# PID.net
KiCad netlist of a schematic drawn in EasyEDA Pro
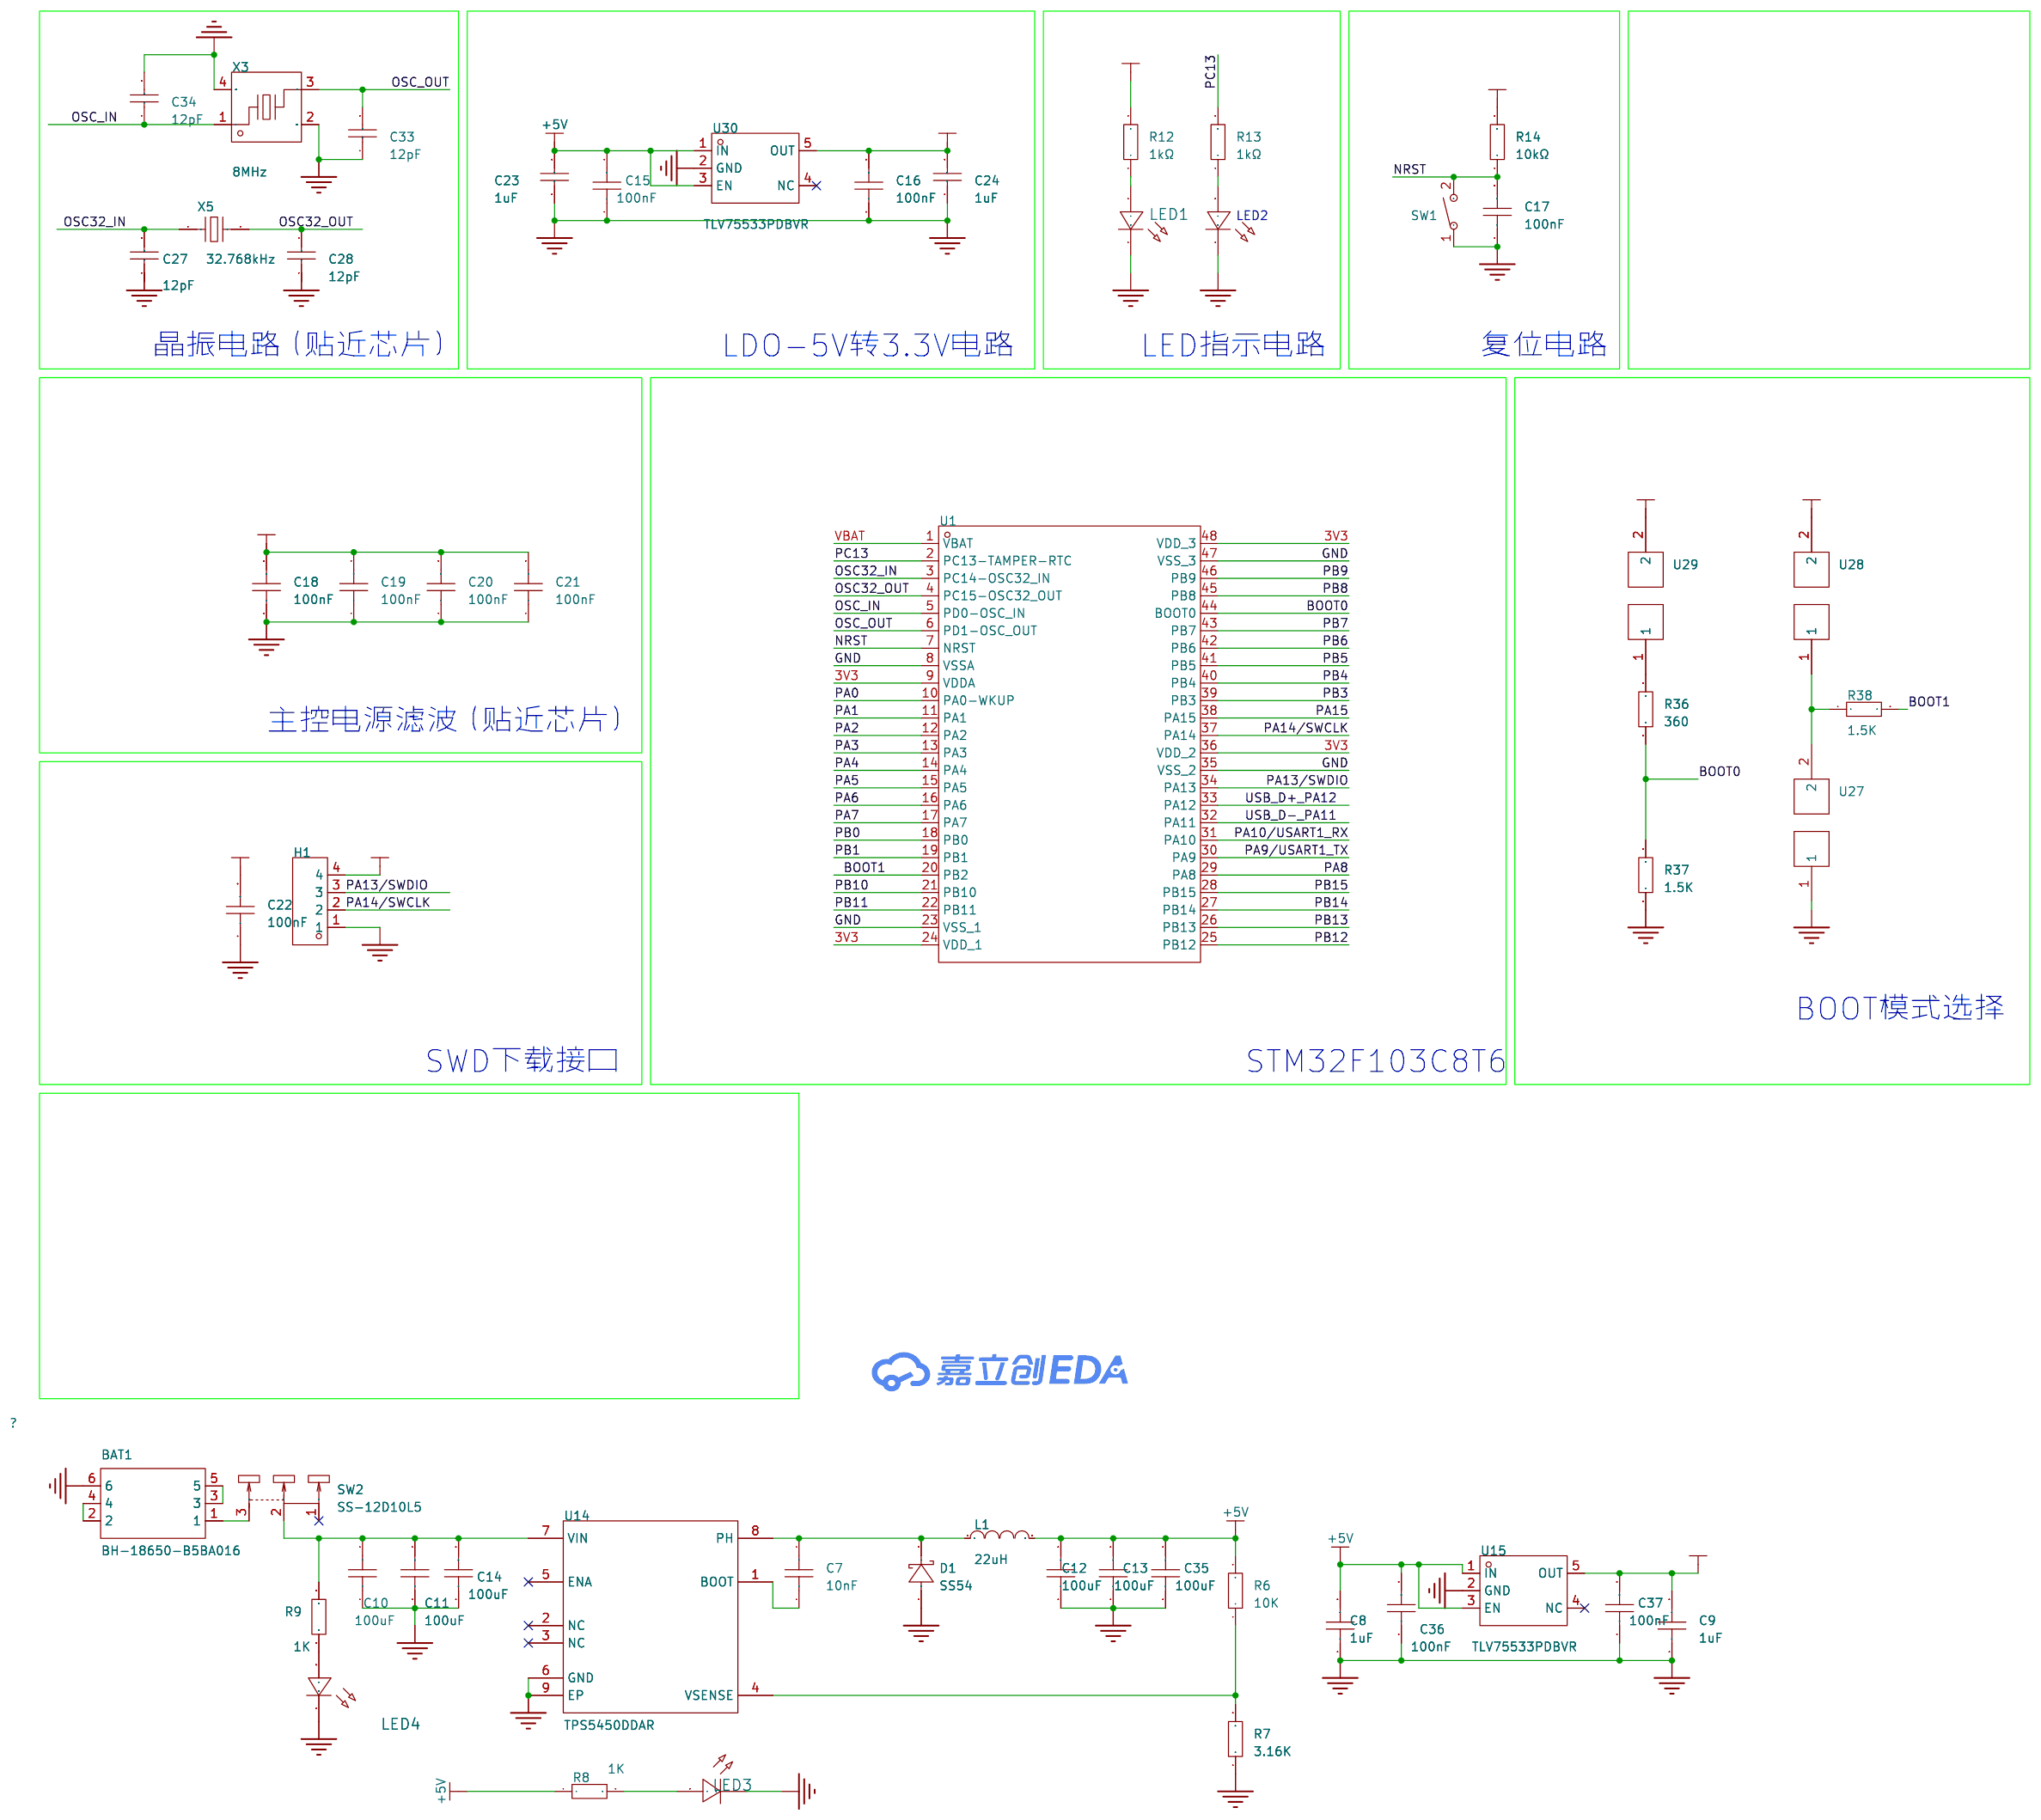
[diagram p0: schematic sheet]

(export (version "E")
  (design (tool "Eeschema 10.0.6"))
  (components
    (comp (ref "BAT1")
      (value "BH-18650-B5BA016")
      (footprint "easyedapro:BAT-SMD_BH-18650-B5BA016")
      (description "连接器类型:电池盒;适用电池规格:-;触点电镀:金;工作温度范围:-25°C~+85°C;")
      (fields (field (name "Manufacturer") "MYOUNG(美阳)"))
      (libsource (lib "easyedapro") (part "BH-18650-B5BA016"))
    )
    (comp (ref "C7")
      (value "100nF")
      (footprint "easyedapro:C0603")
      (libsource (lib "easyedapro") (part "CapAcitance"))
    )
    (comp (ref "C8")
      (value "100nF")
      (footprint "easyedapro:C0603")
      (libsource (lib "easyedapro") (part "CapAcitance"))
    )
    (comp (ref "C9")
      (value "100nF")
      (footprint "easyedapro:C0603")
      (libsource (lib "easyedapro") (part "CapAcitance"))
    )
    (comp (ref "C10")
      (value "100uF")
      (footprint "easyedapro:C1206")
      (description "容值:100uF;精度:±20%;额定电压:10V;材质(温度系数):X5R;")
      (fields
        (field (name "Manufacturer Part") "HGC1206R5107M100NSPJ")
        (field (name "Manufacturer") "Chinocera(华瓷)")
      )
      (libsource (lib "easyedapro") (part "HGC1206R5107M100NSPJ"))
    )
    (comp (ref "C11")
      (value "100uF")
      (footprint "easyedapro:C1206")
      (description "容值:100uF;精度:±20%;额定电压:10V;材质(温度系数):X5R;")
      (fields
        (field (name "Manufacturer Part") "HGC1206R5107M100NSPJ")
        (field (name "Manufacturer") "Chinocera(华瓷)")
      )
      (libsource (lib "easyedapro") (part "HGC1206R5107M100NSPJ"))
    )
    (comp (ref "C12")
      (value "100uF")
      (footprint "easyedapro:C1206")
      (description "容值:100uF;精度:±20%;额定电压:10V;材质(温度系数):X5R;")
      (fields
        (field (name "Manufacturer Part") "HGC1206R5107M100NSPJ")
        (field (name "Manufacturer") "Chinocera(华瓷)")
      )
      (libsource (lib "easyedapro") (part "HGC1206R5107M100NSPJ"))
    )
    (comp (ref "C13")
      (value "100uF")
      (footprint "easyedapro:C1206")
      (description "容值:100uF;精度:±20%;额定电压:10V;材质(温度系数):X5R;")
      (fields
        (field (name "Manufacturer Part") "HGC1206R5107M100NSPJ")
        (field (name "Manufacturer") "Chinocera(华瓷)")
      )
      (libsource (lib "easyedapro") (part "HGC1206R5107M100NSPJ"))
    )
    (comp (ref "C14")
      (value "100uF")
      (footprint "easyedapro:C1206")
      (description "容值:100uF;精度:±20%;额定电压:10V;材质(温度系数):X5R;")
      (fields
        (field (name "Manufacturer Part") "HGC1206R5107M100NSPJ")
        (field (name "Manufacturer") "Chinocera(华瓷)")
      )
      (libsource (lib "easyedapro") (part "HGC1206R5107M100NSPJ"))
    )
    (comp (ref "C15")
      (value "100nF")
      (footprint "easyedapro:C0402")
      (description "容值:100nF;精度:±10%;额定电压:50V;材质(温度系数):X7R;")
      (fields
        (field (name "Manufacturer Part") "GRM155R71H104KE14D")
        (field (name "Manufacturer") "muRata(村田)")
      )
      (libsource (lib "easyedapro") (part "GRM155R71H104KE14D"))
    )
    (comp (ref "C16")
      (value "100nF")
      (footprint "easyedapro:C0402")
      (description "容值:100nF;精度:±10%;额定电压:50V;材质(温度系数):X7R;")
      (fields
        (field (name "Manufacturer Part") "GRM155R71H104KE14D")
        (field (name "Manufacturer") "muRata(村田)")
      )
      (libsource (lib "easyedapro") (part "GRM155R71H104KE14D"))
    )
    (comp (ref "C17")
      (value "100nF")
      (footprint "easyedapro:C0402")
      (description "容值:100nF;精度:±10%;额定电压:50V;材质(温度系数):X7R;")
      (fields
        (field (name "Manufacturer Part") "GRM155R71H104KE14D")
        (field (name "Manufacturer") "muRata(村田)")
      )
      (libsource (lib "easyedapro") (part "GRM155R71H104KE14D"))
    )
    (comp (ref "C18")
      (value "100nF")
      (footprint "easyedapro:C0402")
      (description "容值:100nF;精度:±10%;额定电压:50V;材质(温度系数):X7R;")
      (fields
        (field (name "Manufacturer Part") "GRM155R71H104KE14D")
        (field (name "Manufacturer") "muRata(村田)")
      )
      (libsource (lib "easyedapro") (part "GRM155R71H104KE14D"))
    )
    (comp (ref "C19")
      (value "100nF")
      (footprint "easyedapro:C0402")
      (description "容值:100nF;精度:±10%;额定电压:50V;材质(温度系数):X7R;")
      (fields
        (field (name "Manufacturer Part") "GRM155R71H104KE14D")
        (field (name "Manufacturer") "muRata(村田)")
      )
      (libsource (lib "easyedapro") (part "GRM155R71H104KE14D"))
    )
    (comp (ref "C20")
      (value "100nF")
      (footprint "easyedapro:C0402")
      (description "容值:100nF;精度:±10%;额定电压:50V;材质(温度系数):X7R;")
      (fields
        (field (name "Manufacturer Part") "GRM155R71H104KE14D")
        (field (name "Manufacturer") "muRata(村田)")
      )
      (libsource (lib "easyedapro") (part "GRM155R71H104KE14D"))
    )
    (comp (ref "C21")
      (value "100nF")
      (footprint "easyedapro:C0402")
      (description "容值:100nF;精度:±10%;额定电压:50V;材质(温度系数):X7R;")
      (fields
        (field (name "Manufacturer Part") "GRM155R71H104KE14D")
        (field (name "Manufacturer") "muRata(村田)")
      )
      (libsource (lib "easyedapro") (part "GRM155R71H104KE14D"))
    )
    (comp (ref "C22")
      (value "100nF")
      (footprint "easyedapro:C0402")
      (description "容值:100nF;精度:±10%;额定电压:50V;材质(温度系数):X7R;")
      (fields
        (field (name "Manufacturer Part") "GRM155R71H104KE14D")
        (field (name "Manufacturer") "muRata(村田)")
      )
      (libsource (lib "easyedapro") (part "GRM155R71H104KE14D"))
    )
    (comp (ref "C23")
      (value "1uF")
      (footprint "easyedapro:C0402")
      (description "容值:1uF;精度:±10%;额定电压:10V;材质(温度系数):X5R;")
      (fields
        (field (name "Manufacturer Part") "CL05A105KP5NNNC")
        (field (name "Manufacturer") "SAMSUNG(三星)")
      )
      (libsource (lib "easyedapro") (part "CL05A105KP5NNNC"))
    )
    (comp (ref "C24")
      (value "1uF")
      (footprint "easyedapro:C0402")
      (description "容值:1uF;精度:±10%;额定电压:10V;材质(温度系数):X5R;")
      (fields
        (field (name "Manufacturer Part") "CL05A105KP5NNNC")
        (field (name "Manufacturer") "SAMSUNG(三星)")
      )
      (libsource (lib "easyedapro") (part "CL05A105KP5NNNC"))
    )
    (comp (ref "C27")
      (value "12pF")
      (footprint "easyedapro:C0402")
      (description "容值:12pF;精度:±5%;额定电压:50V;材质(温度系数):C0G;")
      (fields (field (name "Manufacturer Part") "0402CG120J500NT") (field (name "Manufacturer") "FH(风华)"))
      (libsource (lib "easyedapro") (part "0402CG120J500NT"))
    )
    (comp (ref "C28")
      (value "12pF")
      (footprint "easyedapro:C0402")
      (description "容值:12pF;精度:±5%;额定电压:50V;材质(温度系数):C0G;")
      (fields (field (name "Manufacturer Part") "0402CG120J500NT") (field (name "Manufacturer") "FH(风华)"))
      (libsource (lib "easyedapro") (part "0402CG120J500NT"))
    )
    (comp (ref "C33")
      (value "12pF")
      (footprint "easyedapro:C0402")
      (description "容值:12pF;精度:±5%;额定电压:50V;材质(温度系数):C0G;")
      (fields (field (name "Manufacturer Part") "0402CG120J500NT") (field (name "Manufacturer") "FH(风华)"))
      (libsource (lib "easyedapro") (part "0402CG120J500NT"))
    )
    (comp (ref "C34")
      (value "12pF")
      (footprint "easyedapro:C0402")
      (description "容值:12pF;精度:±5%;额定电压:50V;材质(温度系数):C0G;")
      (fields (field (name "Manufacturer Part") "0402CG120J500NT") (field (name "Manufacturer") "FH(风华)"))
      (libsource (lib "easyedapro") (part "0402CG120J500NT"))
    )
    (comp (ref "C35")
      (value "100uF")
      (footprint "easyedapro:C1206")
      (description "容值:100uF;精度:±20%;额定电压:10V;材质(温度系数):X5R;")
      (fields
        (field (name "Manufacturer Part") "HGC1206R5107M100NSPJ")
        (field (name "Manufacturer") "Chinocera(华瓷)")
      )
      (libsource (lib "easyedapro") (part "HGC1206R5107M100NSPJ"))
    )
    (comp (ref "C36")
      (value "100nF")
      (footprint "easyedapro:C0402")
      (description "容值:100nF;精度:±10%;额定电压:50V;材质(温度系数):X7R;")
      (fields
        (field (name "Manufacturer Part") "GRM155R71H104KE14D")
        (field (name "Manufacturer") "muRata(村田)")
      )
      (libsource (lib "easyedapro") (part "GRM155R71H104KE14D"))
    )
    (comp (ref "C37")
      (value "100nF")
      (footprint "easyedapro:C0402")
      (description "容值:100nF;精度:±10%;额定电压:50V;材质(温度系数):X7R;")
      (fields
        (field (name "Manufacturer Part") "GRM155R71H104KE14D")
        (field (name "Manufacturer") "muRata(村田)")
      )
      (libsource (lib "easyedapro") (part "GRM155R71H104KE14D"))
    )
    (comp (ref "D1")
      (value "SS54")
      (footprint "easyedapro:SMA_L4.3-W2.6-LS5.0-FD")
      (description "二极管配置:独立式;正向压降(Vf):550mV@5.0A;直流反向耐压(Vr):40V;整流电流:5A;")
      (fields (field (name "Manufacturer") "宏迦橙"))
      (libsource (lib "easyedapro") (part "SS54_C7420369"))
    )
    (comp (ref "H1")
      (value "~")
      (footprint "easyedapro:HDR-TH_4P-P2.54-V-M")
      (libsource (lib "easyedapro") (part "PZ254V-11-04P"))
    )
    (comp (ref "L1")
      (value "22uH")
      (footprint "easyedapro:IND-SMD_L7.1-W6.6")
      (description "电感值:22uH;精度:±20%;额定电流:3A;")
      (fields
        (field (name "Manufacturer Part") "YSPI0630A-220M")
        (field (name "Manufacturer") "YJYCOIN(益嘉源)")
      )
      (libsource (lib "easyedapro") (part "YSPI0630A-220M"))
    )
    (comp (ref "LED1")
      (value "~")
      (footprint "easyedapro:LED_0603")
      (libsource (lib "easyedapro") (part "LED_R"))
    )
    (comp (ref "LED2")
      (value "~")
      (footprint "easyedapro:LED_0603")
      (libsource (lib "easyedapro") (part "LED_B"))
    )
    (comp (ref "LED3")
      (value "~")
      (footprint "easyedapro:LED_0603")
      (libsource (lib "easyedapro") (part "LED_R"))
    )
    (comp (ref "LED4")
      (value "~")
      (footprint "easyedapro:LED_0603")
      (libsource (lib "easyedapro") (part "LED_R"))
    )
    (comp (ref "R6") (value "10K") (footprint "easyedapro:R0603") (libsource (lib "easyedapro") (part "电阻")))
    (comp (ref "R7") (value "10K") (footprint "easyedapro:R0603") (libsource (lib "easyedapro") (part "电阻")))
    (comp (ref "R8") (value "1K") (footprint "easyedapro:R0603") (libsource (lib "easyedapro") (part "电阻")))
    (comp (ref "R9") (value "1K") (footprint "easyedapro:R0603") (libsource (lib "easyedapro") (part "电阻")))
    (comp (ref "R12")
      (value "1kΩ")
      (footprint "easyedapro:R0402")
      (description "电阻类型:厚膜电阻;阻值:1kΩ;精度:±1%;功率:62.5mW;最大工作电压:50V;温度系数:±100ppm/°C;")
      (fields
        (field (name "Manufacturer Part") "0402WGF1001TCE")
        (field (name "Manufacturer") "UNI-ROYAL(厚声)")
      )
      (libsource (lib "easyedapro") (part "0402WGF1001TCE"))
    )
    (comp (ref "R13")
      (value "1kΩ")
      (footprint "easyedapro:R0402")
      (description "电阻类型:厚膜电阻;阻值:1kΩ;精度:±1%;功率:62.5mW;最大工作电压:50V;温度系数:±100ppm/°C;")
      (fields
        (field (name "Manufacturer Part") "0402WGF1001TCE")
        (field (name "Manufacturer") "UNI-ROYAL(厚声)")
      )
      (libsource (lib "easyedapro") (part "0402WGF1001TCE"))
    )
    (comp (ref "R14")
      (value "10kΩ")
      (footprint "easyedapro:R0402")
      (description "电阻类型:厚膜电阻;阻值:10kΩ;精度:±1%;功率:62.5mW;最大工作电压:50V;温度系数:±100ppm/°C;")
      (fields (field (name "Manufacturer Part") "RC0402FR-0710KL") (field (name "Manufacturer") "YAGEO(国巨)"))
      (libsource (lib "easyedapro") (part "RC0402FR-0710KL"))
    )
    (comp (ref "R36") (value "360") (footprint "easyedapro:R0603") (libsource (lib "easyedapro") (part "电阻")))
    (comp (ref "R37")
      (value "1.5K")
      (footprint "easyedapro:R0603")
      (libsource (lib "easyedapro") (part "电阻"))
    )
    (comp (ref "R38")
      (value "1.5K")
      (footprint "easyedapro:R0603")
      (libsource (lib "easyedapro") (part "电阻"))
    )
    (comp (ref "SW1")
      (value "TS-1101-B-W")
      (footprint "easyedapro:KEY-SMD_2P-L6.0-W3.6-P7.4-LS8.0-L")
      (description "触点电流:50mA;额定电压(DC):12V;绝缘电阻:-;电路结构:单刀单掷;安装方式:立贴;带灯:无;作用力:160gf;机械寿命:5万次;带支架:否;")
      (fields (field (name "Manufacturer") "XKB Connectivity(中国星坤)"))
      (libsource (lib "easyedapro") (part "TS-1101-B-W"))
    )
    (comp (ref "SW2")
      (value "SS-12D10L5")
      (footprint "easyedapro:SW-TH_SS-12D10L5")
      (description "电路结构:单刀双掷;安装方式:直插;开关颜色:黑色;额定电流(DC):3A;额定电压(DC):125V;额定电流(AC):3A;额定电压(AC):125V;机械寿命:1万次;")
      (fields (field (name "Manufacturer") "XKB Connectivity(中国星坤)"))
      (libsource (lib "easyedapro") (part "SS-12D10L5"))
    )
    (comp (ref "U1")
      (value "STM32F103C8T6")
      (footprint "easyedapro:LQFP-48_L7.0-W7.0-P0.50-LS9.0-BL")
      (description "CPU内核:CM3;程序存储容量:64KB;RAM总容量:20KB;GPIO端口数量:37;工作电压范围:2V~3.6V;CPU最大主频:72MHz;程序存储器类型:FLASH;")
      (fields (field (name "Manufacturer") "ST(意法半导体)"))
      (libsource (lib "easyedapro") (part "STM32F103C8T6"))
    )
    (comp (ref "U14")
      (value "TPS5450DDAR")
      (footprint "easyedapro:SOP-8_L4.9-W3.9-P1.27-LS6.0-BL-EP")
      (description "功能类型:降压型;输出类型:可调;工作电压:5.5V~36V;输出电压:1.221V~31.32V;输出电流:5A;")
      (fields (field (name "Manufacturer") "TI(德州仪器)"))
      (libsource (lib "easyedapro") (part "TPS5450DDAR"))
    )
    (comp (ref "U15")
      (value "TLV75533PDBVR")
      (footprint "easyedapro:SOT-23-5_L3.0-W1.7-P0.95-LS2.8-BR")
      (description "输出类型:固定;最大输入电压:5.5V;输出电压:3.3V;输出电流:500mA;电源纹波抑制比(PSRR):52dB;输出极性:正极;")
      (fields (field (name "Manufacturer") "TI(德州仪器)"))
      (libsource (lib "easyedapro") (part "TLV75533PDBVR"))
    )
    (comp (ref "U27") (value "~") (libsource (lib "easyedapro") (part "空焊盘")))
    (comp (ref "U28") (value "~") (libsource (lib "easyedapro") (part "空焊盘")))
    (comp (ref "U29") (value "~") (libsource (lib "easyedapro") (part "空焊盘")))
    (comp (ref "U30")
      (value "TLV75533PDBVR")
      (footprint "easyedapro:SOT-23-5_L3.0-W1.7-P0.95-LS2.8-BR")
      (description "输出类型:固定;最大输入电压:5.5V;输出电压:3.3V;输出电流:500mA;电源纹波抑制比(PSRR):52dB;输出极性:正极;")
      (fields (field (name "Manufacturer") "TI(德州仪器)"))
      (libsource (lib "easyedapro") (part "TLV75533PDBVR"))
    )
    (comp (ref "X3")
      (value "8MHz")
      (footprint "easyedapro:CRYSTAL-SMD_4P-L3.2-W2.5-BL-1")
      (description "晶振类型:贴片晶振;频率:8MHz;常温频差:±10ppm;外接负载电容:12pF;频率稳定度(全温):±20ppm;")
      (fields
        (field (name "Manufacturer Part") "XL2EL89COI-111YLC-8M")
        (field (name "Manufacturer") "YXC(扬兴晶振)")
      )
      (libsource (lib "easyedapro") (part "XL2EL89COI-111YLC-8M"))
    )
    (comp (ref "X5")
      (value "32.768kHz")
      (footprint "easyedapro:OSC-SMD_L3.2-W1.5")
      (description "晶振类型:贴片晶振;频率:32.768kHz;常温频差:±20ppm;外接负载电容:12.5pF;频率稳定度(全温):-;")
      (fields (field (name "Manufacturer Part") "X321532768KGD2SI") (field (name "Manufacturer") "YXC(扬兴晶振)"))
      (libsource (lib "easyedapro") (part "X321532768KGD2SI"))
    )
  )
  (nets
    (net (code "1") (name "+5V") (class "Default")
      (node (ref "C12") (pin "2") (pinfunction "2_2") (pintype "unspecified"))
      (node (ref "C13") (pin "2") (pinfunction "2_2") (pintype "unspecified"))
      (node (ref "C15") (pin "2") (pinfunction "2_2") (pintype "unspecified"))
      (node (ref "C23") (pin "2") (pinfunction "2_2") (pintype "input"))
      (node (ref "C35") (pin "2") (pinfunction "2_2") (pintype "unspecified"))
      (node (ref "C36") (pin "2") (pinfunction "2_2") (pintype "unspecified"))
      (node (ref "C8") (pin "2") (pinfunction "2_2") (pintype "input"))
      (node (ref "L1") (pin "2") (pinfunction "2_2") (pintype "unspecified"))
      (node (ref "R6") (pin "2") (pinfunction "2_2") (pintype "input"))
      (node (ref "R8") (pin "1") (pinfunction "1_1") (pintype "input"))
      (node (ref "U15") (pin "1") (pinfunction "IN_1") (pintype "unspecified"))
      (node (ref "U15") (pin "3") (pinfunction "EN_3") (pintype "unspecified"))
      (node (ref "U30") (pin "1") (pinfunction "IN_1") (pintype "unspecified"))
      (node (ref "U30") (pin "3") (pinfunction "EN_3") (pintype "unspecified"))
    )
    (net (code "2") (name "/BOOT0") (class "Default")
      (node (ref "R36") (pin "1") (pinfunction "1_1") (pintype "input"))
      (node (ref "R37") (pin "2") (pinfunction "2_2") (pintype "input"))
      (node (ref "U1") (pin "44") (pinfunction "BOOT0_44") (pintype "unspecified"))
    )
    (net (code "3") (name "/BOOT1") (class "Default")
      (node (ref "R38") (pin "2") (pinfunction "2_2") (pintype "input"))
      (node (ref "U1") (pin "20") (pinfunction "PB2_20") (pintype "unspecified"))
    )
    (net (code "4") (name "/NRST") (class "Default")
      (node (ref "C17") (pin "2") (pinfunction "2_2") (pintype "unspecified"))
      (node (ref "R14") (pin "1") (pinfunction "1_1") (pintype "input"))
      (node (ref "SW1") (pin "2") (pinfunction "2_2") (pintype "input"))
      (node (ref "U1") (pin "7") (pinfunction "NRST_7") (pintype "unspecified"))
    )
    (net (code "5") (name "/OSC32_IN") (class "Default")
      (node (ref "C27") (pin "2") (pinfunction "2_2") (pintype "input"))
      (node (ref "U1") (pin "3") (pinfunction "PC14-OSC32_IN_3") (pintype "unspecified"))
      (node (ref "X5") (pin "1") (pinfunction "1_1") (pintype "input"))
    )
    (net (code "6") (name "/OSC32_OUT") (class "Default")
      (node (ref "C28") (pin "2") (pinfunction "2_2") (pintype "input"))
      (node (ref "U1") (pin "4") (pinfunction "PC15-OSC32_OUT_4") (pintype "unspecified"))
      (node (ref "X5") (pin "2") (pinfunction "2_2") (pintype "input"))
    )
    (net (code "7") (name "/OSC_IN") (class "Default")
      (node (ref "C34") (pin "1") (pinfunction "1_1") (pintype "input"))
      (node (ref "U1") (pin "5") (pinfunction "PD0-OSC_IN_5") (pintype "unspecified"))
      (node (ref "X3") (pin "1") (pinfunction "1_1") (pintype "input"))
    )
    (net (code "8") (name "/OSC_OUT") (class "Default")
      (node (ref "C33") (pin "2") (pinfunction "2_2") (pintype "input"))
      (node (ref "U1") (pin "6") (pinfunction "PD1-OSC_OUT_6") (pintype "unspecified"))
      (node (ref "X3") (pin "3") (pinfunction "3_3") (pintype "input"))
    )
    (net (code "9") (name "/PA0") (class "Default")
      (node (ref "U1") (pin "10") (pinfunction "PA0-WKUP_10") (pintype "unspecified"))
    )
    (net (code "10") (name "/PA1") (class "Default")
      (node (ref "U1") (pin "11") (pinfunction "PA1_11") (pintype "unspecified"))
    )
    (net (code "11") (name "/PA2") (class "Default")
      (node (ref "U1") (pin "12") (pinfunction "PA2_12") (pintype "unspecified"))
    )
    (net (code "12") (name "/PA3") (class "Default")
      (node (ref "U1") (pin "13") (pinfunction "PA3_13") (pintype "unspecified"))
    )
    (net (code "13") (name "/PA4") (class "Default")
      (node (ref "U1") (pin "14") (pinfunction "PA4_14") (pintype "unspecified"))
    )
    (net (code "14") (name "/PA5") (class "Default")
      (node (ref "U1") (pin "15") (pinfunction "PA5_15") (pintype "unspecified"))
    )
    (net (code "15") (name "/PA6") (class "Default")
      (node (ref "U1") (pin "16") (pinfunction "PA6_16") (pintype "unspecified"))
    )
    (net (code "16") (name "/PA7") (class "Default")
      (node (ref "U1") (pin "17") (pinfunction "PA7_17") (pintype "unspecified"))
    )
    (net (code "17") (name "/PA8") (class "Default")
      (node (ref "U1") (pin "29") (pinfunction "PA8_29") (pintype "unspecified"))
    )
    (net (code "18") (name "/PA9{slash}USART1_TX") (class "Default")
      (node (ref "U1") (pin "30") (pinfunction "PA9_30") (pintype "unspecified"))
    )
    (net (code "19") (name "/PA10{slash}USART1_RX") (class "Default")
      (node (ref "U1") (pin "31") (pinfunction "PA10_31") (pintype "unspecified"))
    )
    (net (code "20") (name "/PA13{slash}SWDIO") (class "Default")
      (node (ref "H1") (pin "3") (pinfunction "3_3") (pintype "input"))
      (node (ref "U1") (pin "34") (pinfunction "PA13_34") (pintype "unspecified"))
    )
    (net (code "21") (name "/PA14{slash}SWCLK") (class "Default")
      (node (ref "H1") (pin "2") (pinfunction "2_2") (pintype "input"))
      (node (ref "U1") (pin "37") (pinfunction "PA14_37") (pintype "unspecified"))
    )
    (net (code "22") (name "/PA15") (class "Default")
      (node (ref "U1") (pin "38") (pinfunction "PA15_38") (pintype "unspecified"))
    )
    (net (code "23") (name "/PB0") (class "Default")
      (node (ref "U1") (pin "18") (pinfunction "PB0_18") (pintype "unspecified"))
    )
    (net (code "24") (name "/PB1") (class "Default")
      (node (ref "U1") (pin "19") (pinfunction "PB1_19") (pintype "unspecified"))
    )
    (net (code "25") (name "/PB3") (class "Default")
      (node (ref "U1") (pin "39") (pinfunction "PB3_39") (pintype "unspecified"))
    )
    (net (code "26") (name "/PB4") (class "Default")
      (node (ref "U1") (pin "40") (pinfunction "PB4_40") (pintype "unspecified"))
    )
    (net (code "27") (name "/PB5") (class "Default")
      (node (ref "U1") (pin "41") (pinfunction "PB5_41") (pintype "unspecified"))
    )
    (net (code "28") (name "/PB6") (class "Default")
      (node (ref "U1") (pin "42") (pinfunction "PB6_42") (pintype "unspecified"))
    )
    (net (code "29") (name "/PB7") (class "Default")
      (node (ref "U1") (pin "43") (pinfunction "PB7_43") (pintype "unspecified"))
    )
    (net (code "30") (name "/PB8") (class "Default")
      (node (ref "U1") (pin "45") (pinfunction "PB8_45") (pintype "unspecified"))
    )
    (net (code "31") (name "/PB9") (class "Default")
      (node (ref "U1") (pin "46") (pinfunction "PB9_46") (pintype "unspecified"))
    )
    (net (code "32") (name "/PB10") (class "Default")
      (node (ref "U1") (pin "21") (pinfunction "PB10_21") (pintype "unspecified"))
    )
    (net (code "33") (name "/PB11") (class "Default")
      (node (ref "U1") (pin "22") (pinfunction "PB11_22") (pintype "unspecified"))
    )
    (net (code "34") (name "/PB12") (class "Default")
      (node (ref "U1") (pin "25") (pinfunction "PB12_25") (pintype "unspecified"))
    )
    (net (code "35") (name "/PB13") (class "Default")
      (node (ref "U1") (pin "26") (pinfunction "PB13_26") (pintype "unspecified"))
    )
    (net (code "36") (name "/PB14") (class "Default")
      (node (ref "U1") (pin "27") (pinfunction "PB14_27") (pintype "unspecified"))
    )
    (net (code "37") (name "/PB15") (class "Default")
      (node (ref "U1") (pin "28") (pinfunction "PB15_28") (pintype "unspecified"))
    )
    (net (code "38") (name "/PC13") (class "Default")
      (node (ref "R13") (pin "2") (pinfunction "2_2") (pintype "input"))
      (node (ref "U1") (pin "2") (pinfunction "PC13-TAMPER-RTC_2") (pintype "unspecified"))
    )
    (net (code "39") (name "/USB_D+_PA12") (class "Default")
      (node (ref "U1") (pin "33") (pinfunction "PA12_33") (pintype "unspecified"))
    )
    (net (code "40") (name "/USB_D-_PA11") (class "Default")
      (node (ref "U1") (pin "32") (pinfunction "PA11_32") (pintype "unspecified"))
    )
    (net (code "41") (name "/VBAT") (class "Default")
      (node (ref "U1") (pin "1") (pinfunction "VBAT_1") (pintype "unspecified"))
    )
    (net (code "42") (name "3V3") (class "Default")
      (node (ref "C18") (pin "2") (pinfunction "2_2") (pintype "unspecified"))
      (node (ref "C19") (pin "2") (pinfunction "2_2") (pintype "unspecified"))
      (node (ref "C20") (pin "2") (pinfunction "2_2") (pintype "unspecified"))
      (node (ref "C21") (pin "2") (pinfunction "2_2") (pintype "unspecified"))
      (node (ref "C22") (pin "2") (pinfunction "2_2") (pintype "unspecified"))
      (node (ref "C37") (pin "2") (pinfunction "2_2") (pintype "unspecified"))
      (node (ref "C9") (pin "2") (pinfunction "2_2") (pintype "input"))
      (node (ref "H1") (pin "4") (pinfunction "4_4") (pintype "input"))
      (node (ref "R12") (pin "2") (pinfunction "2_2") (pintype "input"))
      (node (ref "R14") (pin "2") (pinfunction "2_2") (pintype "input"))
      (node (ref "U1") (pin "24") (pinfunction "VDD_1_24") (pintype "unspecified"))
      (node (ref "U1") (pin "36") (pinfunction "VDD_2_36") (pintype "unspecified"))
      (node (ref "U1") (pin "48") (pinfunction "VDD_3_48") (pintype "unspecified"))
      (node (ref "U1") (pin "9") (pinfunction "VDDA_9") (pintype "unspecified"))
      (node (ref "U15") (pin "5") (pinfunction "OUT_5") (pintype "unspecified"))
      (node (ref "U28") (pin "2") (pinfunction "2_2") (pintype "input"))
      (node (ref "U29") (pin "2") (pinfunction "2_2") (pintype "input"))
    )
    (net (code "43") (name "ADC_3V3") (class "Default")
      (node (ref "C16") (pin "2") (pinfunction "2_2") (pintype "unspecified"))
      (node (ref "C24") (pin "2") (pinfunction "2_2") (pintype "input"))
      (node (ref "U30") (pin "5") (pinfunction "OUT_5") (pintype "unspecified"))
    )
    (net (code "44") (name "GND") (class "Default")
      (node (ref "BAT1") (pin "6") (pinfunction "6_6") (pintype "unspecified"))
      (node (ref "C10") (pin "1") (pinfunction "1_1") (pintype "unspecified"))
      (node (ref "C11") (pin "1") (pinfunction "1_1") (pintype "unspecified"))
      (node (ref "C12") (pin "1") (pinfunction "1_1") (pintype "unspecified"))
      (node (ref "C13") (pin "1") (pinfunction "1_1") (pintype "unspecified"))
      (node (ref "C14") (pin "1") (pinfunction "1_1") (pintype "unspecified"))
      (node (ref "C15") (pin "1") (pinfunction "1_1") (pintype "unspecified"))
      (node (ref "C16") (pin "1") (pinfunction "1_1") (pintype "unspecified"))
      (node (ref "C17") (pin "1") (pinfunction "1_1") (pintype "unspecified"))
      (node (ref "C18") (pin "1") (pinfunction "1_1") (pintype "unspecified"))
      (node (ref "C19") (pin "1") (pinfunction "1_1") (pintype "unspecified"))
      (node (ref "C20") (pin "1") (pinfunction "1_1") (pintype "unspecified"))
      (node (ref "C21") (pin "1") (pinfunction "1_1") (pintype "unspecified"))
      (node (ref "C22") (pin "1") (pinfunction "1_1") (pintype "unspecified"))
      (node (ref "C23") (pin "1") (pinfunction "1_1") (pintype "input"))
      (node (ref "C24") (pin "1") (pinfunction "1_1") (pintype "input"))
      (node (ref "C27") (pin "1") (pinfunction "1_1") (pintype "input"))
      (node (ref "C28") (pin "1") (pinfunction "1_1") (pintype "input"))
      (node (ref "C33") (pin "1") (pinfunction "1_1") (pintype "input"))
      (node (ref "C34") (pin "2") (pinfunction "2_2") (pintype "input"))
      (node (ref "C35") (pin "1") (pinfunction "1_1") (pintype "unspecified"))
      (node (ref "C36") (pin "1") (pinfunction "1_1") (pintype "unspecified"))
      (node (ref "C37") (pin "1") (pinfunction "1_1") (pintype "unspecified"))
      (node (ref "C8") (pin "1") (pinfunction "1_1") (pintype "input"))
      (node (ref "C9") (pin "1") (pinfunction "1_1") (pintype "input"))
      (node (ref "D1") (pin "1") (pinfunction "A_1") (pintype "unspecified"))
      (node (ref "H1") (pin "1") (pinfunction "1_1") (pintype "input"))
      (node (ref "LED1") (pin "1") (pinfunction "C_1") (pintype "input"))
      (node (ref "LED2") (pin "1") (pinfunction "C_1") (pintype "input"))
      (node (ref "LED3") (pin "1") (pinfunction "C_1") (pintype "input"))
      (node (ref "LED4") (pin "1") (pinfunction "C_1") (pintype "input"))
      (node (ref "R37") (pin "1") (pinfunction "1_1") (pintype "input"))
      (node (ref "R7") (pin "1") (pinfunction "1_1") (pintype "input"))
      (node (ref "SW1") (pin "1") (pinfunction "1_1") (pintype "input"))
      (node (ref "U1") (pin "23") (pinfunction "VSS_1_23") (pintype "unspecified"))
      (node (ref "U1") (pin "35") (pinfunction "VSS_2_35") (pintype "unspecified"))
      (node (ref "U1") (pin "47") (pinfunction "VSS_3_47") (pintype "unspecified"))
      (node (ref "U1") (pin "8") (pinfunction "VSSA_8") (pintype "unspecified"))
      (node (ref "U14") (pin "6") (pinfunction "GND_6") (pintype "unspecified"))
      (node (ref "U14") (pin "9") (pinfunction "EP_9") (pintype "unspecified"))
      (node (ref "U15") (pin "2") (pinfunction "GND_2") (pintype "unspecified"))
      (node (ref "U27") (pin "1") (pinfunction "1_1") (pintype "input"))
      (node (ref "U30") (pin "2") (pinfunction "GND_2") (pintype "unspecified"))
      (node (ref "X3") (pin "2") (pinfunction "GND_2") (pintype "input"))
      (node (ref "X3") (pin "4") (pinfunction "GND_4") (pintype "input"))
    )
    (net (code "45") (name "Net-(BAT1-Pad1)") (class "Default")
      (node (ref "BAT1") (pin "1") (pinfunction "1_1") (pintype "unspecified"))
      (node (ref "SW2") (pin "3") (pinfunction "3_3") (pintype "unspecified"))
    )
    (net (code "46") (name "Net-(BAT1-Pad2)") (class "Default")
      (node (ref "BAT1") (pin "2") (pinfunction "2_2") (pintype "unspecified"))
      (node (ref "BAT1") (pin "4") (pinfunction "4_4") (pintype "unspecified"))
    )
    (net (code "47") (name "Net-(BAT1-Pad3)") (class "Default")
      (node (ref "BAT1") (pin "3") (pinfunction "3_3") (pintype "unspecified"))
      (node (ref "BAT1") (pin "5") (pinfunction "5_5") (pintype "unspecified"))
    )
    (net (code "48") (name "Net-(D1-K)") (class "Default")
      (node (ref "C7") (pin "2") (pinfunction "2_2") (pintype "input"))
      (node (ref "D1") (pin "2") (pinfunction "K_2") (pintype "unspecified"))
      (node (ref "L1") (pin "1") (pinfunction "1_1") (pintype "unspecified"))
      (node (ref "U14") (pin "8") (pinfunction "PH_8") (pintype "output"))
    )
    (net (code "49") (name "Net-(LED1-A)") (class "Default")
      (node (ref "LED1") (pin "2") (pinfunction "A_2") (pintype "input"))
      (node (ref "R12") (pin "1") (pinfunction "1_1") (pintype "input"))
    )
    (net (code "50") (name "Net-(LED2-A)") (class "Default")
      (node (ref "LED2") (pin "2") (pinfunction "A_2") (pintype "input"))
      (node (ref "R13") (pin "1") (pinfunction "1_1") (pintype "input"))
    )
    (net (code "51") (name "Net-(LED3-A)") (class "Default")
      (node (ref "LED3") (pin "2") (pinfunction "A_2") (pintype "input"))
      (node (ref "R8") (pin "2") (pinfunction "2_2") (pintype "input"))
    )
    (net (code "52") (name "Net-(LED4-A)") (class "Default")
      (node (ref "LED4") (pin "2") (pinfunction "A_2") (pintype "input"))
      (node (ref "R9") (pin "1") (pinfunction "1_1") (pintype "input"))
    )
    (net (code "53") (name "Net-(R36-Pad2)") (class "Default")
      (node (ref "R36") (pin "2") (pinfunction "2_2") (pintype "input"))
      (node (ref "U29") (pin "1") (pinfunction "1_1") (pintype "input"))
    )
    (net (code "54") (name "Net-(R38-Pad1)") (class "Default")
      (node (ref "R38") (pin "1") (pinfunction "1_1") (pintype "input"))
      (node (ref "U27") (pin "2") (pinfunction "2_2") (pintype "input"))
      (node (ref "U28") (pin "1") (pinfunction "1_1") (pintype "input"))
    )
    (net (code "55") (name "Net-(U14-BOOT)") (class "Default")
      (node (ref "C7") (pin "1") (pinfunction "1_1") (pintype "input"))
      (node (ref "U14") (pin "1") (pinfunction "BOOT_1") (pintype "unspecified"))
    )
    (net (code "56") (name "Net-(U14-VIN)") (class "Default")
      (node (ref "C10") (pin "2") (pinfunction "2_2") (pintype "unspecified"))
      (node (ref "C11") (pin "2") (pinfunction "2_2") (pintype "unspecified"))
      (node (ref "C14") (pin "2") (pinfunction "2_2") (pintype "unspecified"))
      (node (ref "R9") (pin "2") (pinfunction "2_2") (pintype "input"))
      (node (ref "SW2") (pin "2") (pinfunction "2_2") (pintype "unspecified"))
      (node (ref "U14") (pin "7") (pinfunction "VIN_7") (pintype "input"))
    )
    (net (code "57") (name "Net-(U14-VSENSE)") (class "Default")
      (node (ref "R6") (pin "1") (pinfunction "1_1") (pintype "input"))
      (node (ref "R7") (pin "2") (pinfunction "2_2") (pintype "input"))
      (node (ref "U14") (pin "4") (pinfunction "VSENSE_4") (pintype "output"))
    )
    (net (code "58") (name "unconnected-(SW2-Pad1)") (class "Default")
      (node (ref "SW2") (pin "1") (pinfunction "1_1") (pintype "unspecified+no_connect"))
    )
    (net (code "59") (name "unconnected-(U14-ENA-Pad5)") (class "Default")
      (node (ref "U14") (pin "5") (pinfunction "ENA_5") (pintype "input+no_connect"))
    )
    (net (code "60") (name "unconnected-(U14-NC-Pad2)") (class "Default")
      (node (ref "U14") (pin "2") (pinfunction "NC_2") (pintype "unspecified+no_connect"))
    )
    (net (code "61") (name "unconnected-(U14-NC-Pad3)") (class "Default")
      (node (ref "U14") (pin "3") (pinfunction "NC_3") (pintype "unspecified+no_connect"))
    )
    (net (code "62") (name "unconnected-(U15-NC-Pad4)") (class "Default")
      (node (ref "U15") (pin "4") (pinfunction "NC_4") (pintype "unspecified+no_connect"))
    )
    (net (code "63") (name "unconnected-(U30-NC-Pad4)") (class "Default")
      (node (ref "U30") (pin "4") (pinfunction "NC_4") (pintype "unspecified+no_connect"))
    )
  )
)
